# CurrentSensors.net
KiCad netlist of a schematic drawn in Altium Designer
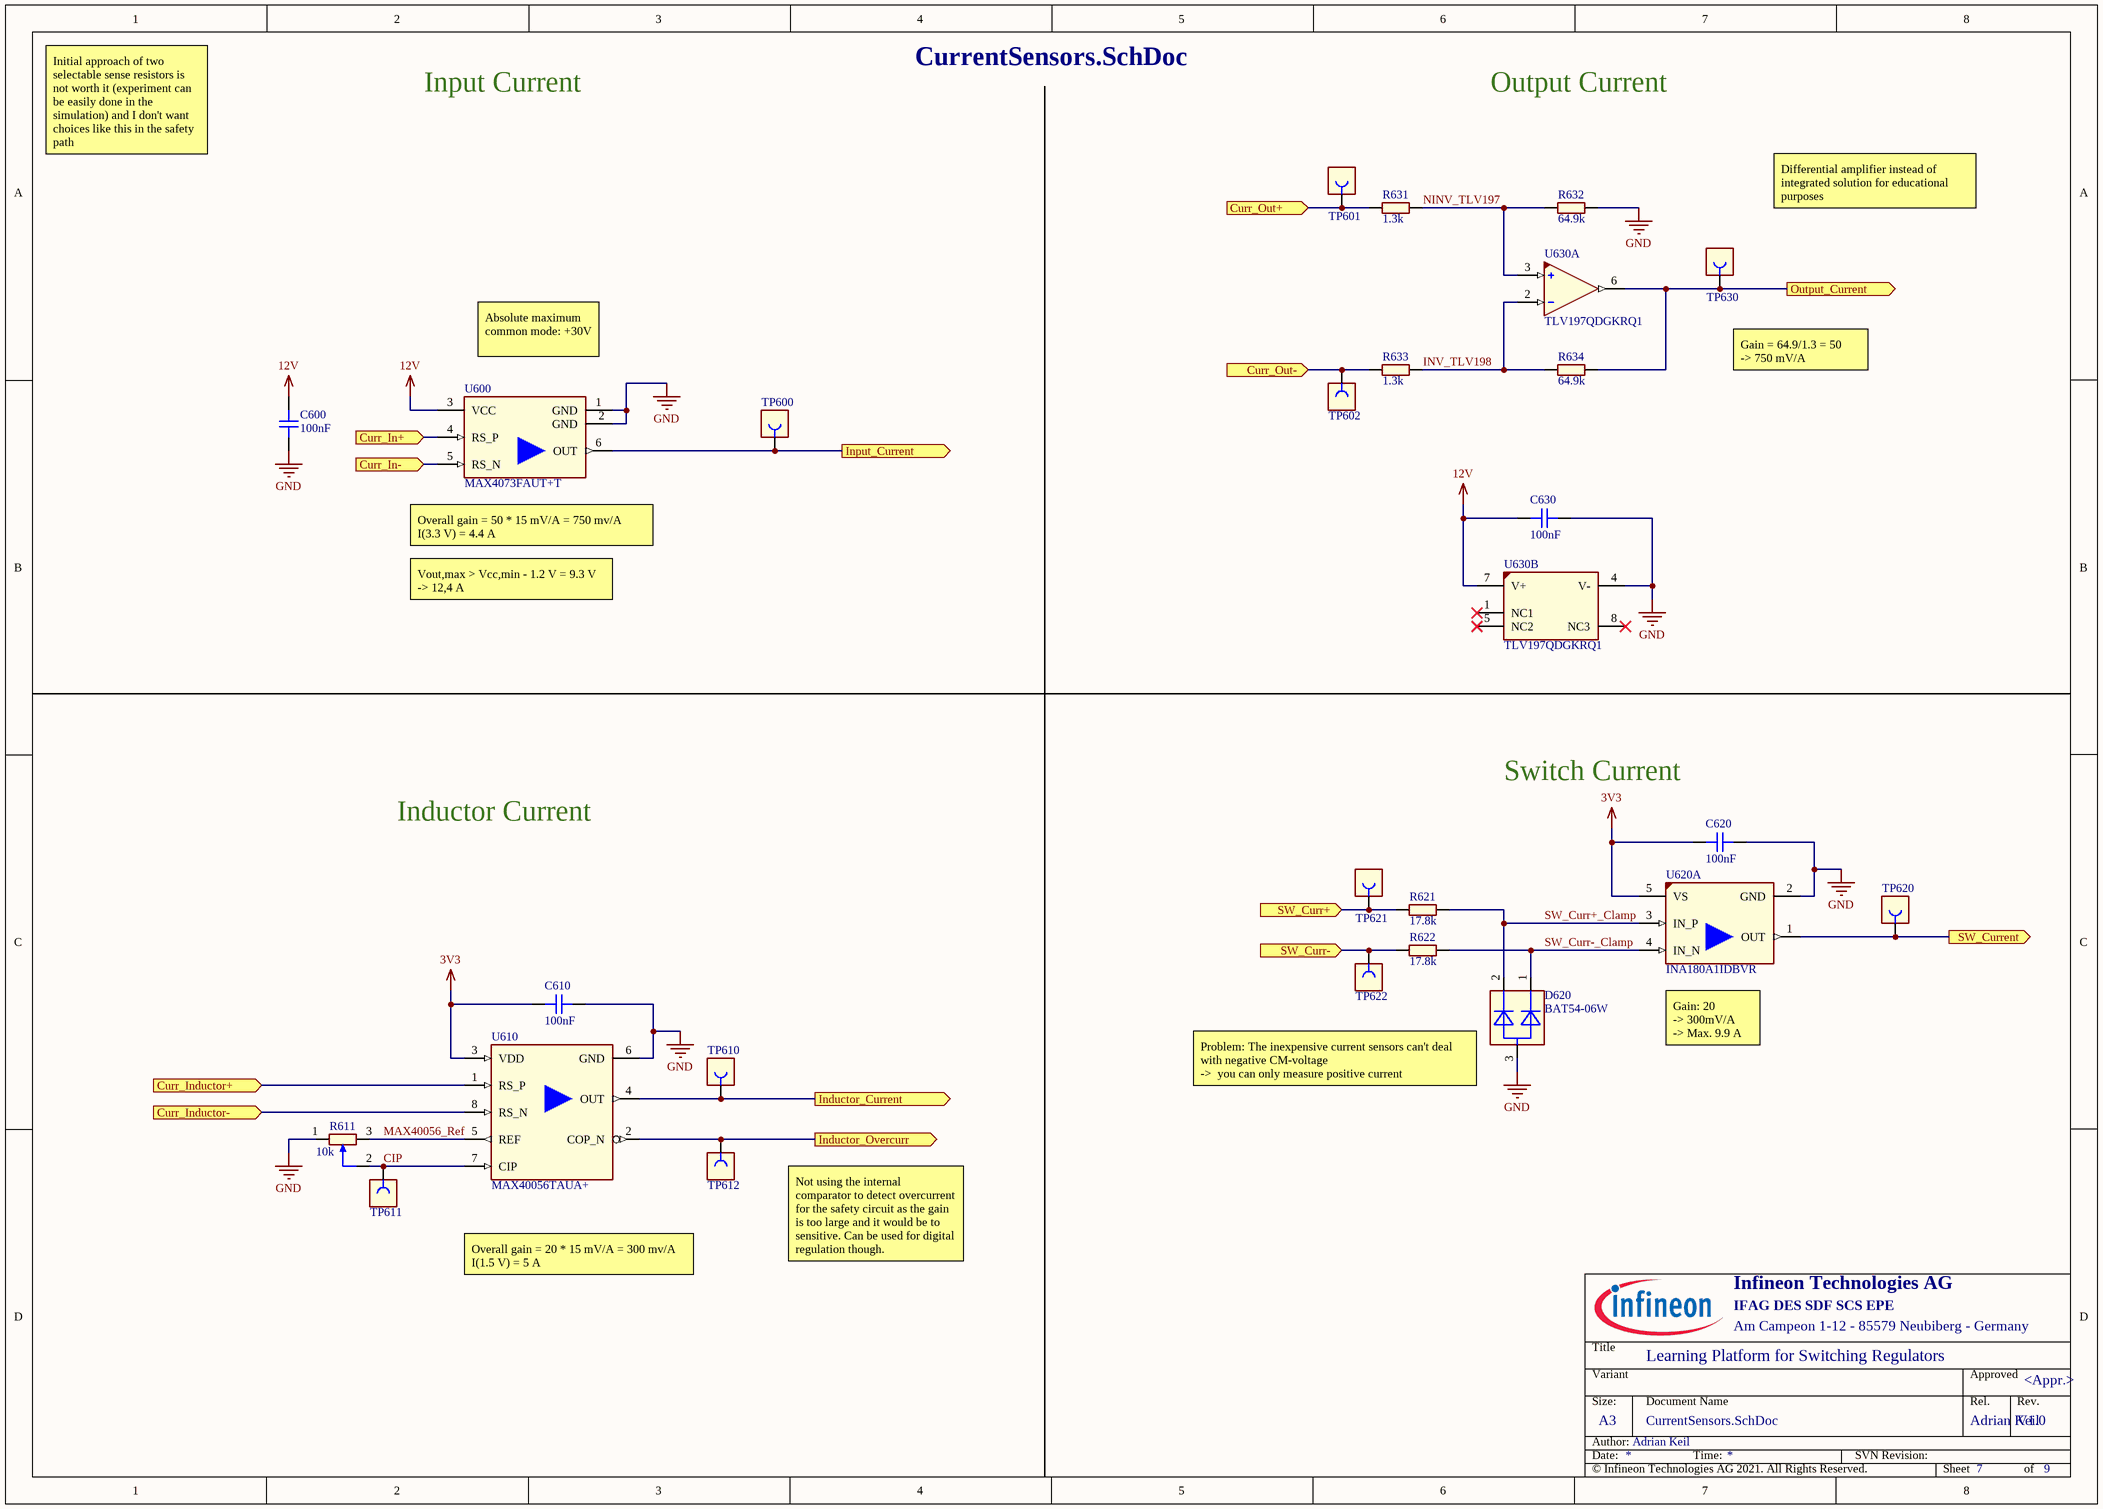
[diagram p0: CurrentSensors.SchDoc]

(export (version "E")
  (design (tool "Eeschema 10.0.6"))
  (components
    (comp (ref "C600")
      (value "100nF")
      (footprint "CAPC1608X90N-2")
      (description "CAP / CERA / 100nF / 50V / 10% / X7R (EIA) / -55°C to 125°C / 0603 / SMD / -")
      (fields (field (name "MANUFACTURER") "AVX"))
      (libsource (lib "PCBLibraryData") (part "CAP-SGL-STD-02P_00000001"))
    )
    (comp (ref "C610")
      (value "100nF")
      (footprint "CAPC1608X90N-2")
      (description "CAP / CERA / 100nF / 50V / 10% / X7R (EIA) / -55°C to 125°C / 0603 / SMD / -")
      (fields (field (name "MANUFACTURER") "AVX"))
      (libsource (lib "PCBLibraryData") (part "CAP-SGL-STD-02P_00000001"))
    )
    (comp (ref "C620")
      (value "100nF")
      (footprint "CAPC1608X90N-2")
      (description "CAP / CERA / 100nF / 50V / 10% / X7R (EIA) / -55°C to 125°C / 0603 / SMD / -")
      (fields (field (name "MANUFACTURER") "AVX"))
      (libsource (lib "PCBLibraryData") (part "CAP-SGL-STD-02P_00000001"))
    )
    (comp (ref "C630")
      (value "100nF")
      (footprint "CAPC1608X90N-2")
      (description "CAP / CERA / 100nF / 50V / 10% / X7R (EIA) / -55°C to 125°C / 0603 / SMD / -")
      (fields (field (name "MANUFACTURER") "AVX"))
      (libsource (lib "PCBLibraryData") (part "CAP-SGL-STD-02P_00000001"))
    )
    (comp (ref "D620")
      (value "BAT54-06W")
      (footprint "SOT65P210X100-3N-1-V")
      (description "Silicon Schottky Diodes")
      (fields (field (name "MANUFACTURER") "Infineon Technologies"))
      (libsource (lib "PCBLibraryData") (part "d_dual_c1c2a3_3p"))
    )
    (comp (ref "R611")
      (value "10k")
      (footprint "POT-SMD-3361P")
      (fields (field (name "MANUFACTURER") "Bourns"))
      (libsource (lib "PCBLibraryData") (part "RES-SGL-VAR-03P_00000026"))
    )
    (comp (ref "R621")
      (value "17.8k")
      (footprint "RESC1609X50N")
      (description "RES / STD / 17.8k / 100mW / 1% / 100ppm/K / -55°C to 155°C / 0603 / SMD / -")
      (fields (field (name "LEGACY PARTNUMBER") "RES01801283") (field (name "MANUFACTURER") "Vishay"))
      (libsource (lib "") (part "RES-SGL-STD-02P_00000006_1"))
    )
    (comp (ref "R622")
      (value "17.8k")
      (footprint "RESC1609X50N")
      (description "RES / STD / 17.8k / 100mW / 1% / 100ppm/K / -55°C to 155°C / 0603 / SMD / -")
      (fields (field (name "LEGACY PARTNUMBER") "RES01801283") (field (name "MANUFACTURER") "Vishay"))
      (libsource (lib "") (part "RES-SGL-STD-02P_00000006_1"))
    )
    (comp (ref "R631")
      (value "1.3k")
      (footprint "RESC1609X50N")
      (description "RES / STD / 1.3k / 100mW / 1% / 100ppm/K / -55°C to 155°C / 0603 / SMD / -")
      (fields (field (name "LEGACY PARTNUMBER") "RES01801155") (field (name "MANUFACTURER") "Vishay"))
      (libsource (lib "PCBLibraryData") (part "RES-SGL-STD-02P_00000006"))
    )
    (comp (ref "R632")
      (value "64.9k")
      (footprint "RESC1609X50N")
      (description "RES / STD / 64.9k / 100mW / 1% / 100ppm/K / -55°C to 155°C / 0603 / SMD / -")
      (fields (field (name "LEGACY PARTNUMBER") "RES01801350") (field (name "MANUFACTURER") "Vishay"))
      (libsource (lib "") (part "RES-SGL-STD-02P_00000006_1"))
    )
    (comp (ref "R633")
      (value "1.3k")
      (footprint "RESC1609X50N")
      (description "RES / STD / 1.3k / 100mW / 1% / 100ppm/K / -55°C to 155°C / 0603 / SMD / -")
      (fields (field (name "LEGACY PARTNUMBER") "RES01801155") (field (name "MANUFACTURER") "Vishay"))
      (libsource (lib "PCBLibraryData") (part "RES-SGL-STD-02P_00000006"))
    )
    (comp (ref "R634")
      (value "64.9k")
      (footprint "RESC1609X50N")
      (description "RES / STD / 64.9k / 100mW / 1% / 100ppm/K / -55°C to 155°C / 0603 / SMD / -")
      (fields (field (name "LEGACY PARTNUMBER") "RES01801350") (field (name "MANUFACTURER") "Vishay"))
      (libsource (lib "PCBLibraryData") (part "RES-SGL-STD-02P_00000006"))
    )
    (comp (ref "TP600")
      (value "S1751-46R")
      (footprint "CON-SMD-TT-S1751-46")
      (description "Test Terminal, Surface Mount (Tape and Reeled Components)")
      (fields (field (name "LEGACY PARTNUMBER") "CON01501015") (field (name "MANUFACTURER") "Harwin"))
      (libsource (lib "") (part "connector_1_f_1"))
    )
    (comp (ref "TP601")
      (value "S1751-46R")
      (footprint "CON-SMD-TT-S1751-46")
      (description "Test Terminal, Surface Mount (Tape and Reeled Components)")
      (fields (field (name "LEGACY PARTNUMBER") "CON01501015") (field (name "MANUFACTURER") "Harwin"))
      (libsource (lib "") (part "connector_1_f_1"))
    )
    (comp (ref "TP602")
      (value "S1751-46R")
      (footprint "CON-SMD-TT-S1751-46")
      (description "Test Terminal, Surface Mount (Tape and Reeled Components)")
      (fields (field (name "LEGACY PARTNUMBER") "CON01501015") (field (name "MANUFACTURER") "Harwin"))
      (libsource (lib "PCBLibraryData") (part "connector_1_f"))
    )
    (comp (ref "TP610")
      (value "S1751-46R")
      (footprint "CON-SMD-TT-S1751-46")
      (description "Test Terminal, Surface Mount (Tape and Reeled Components)")
      (fields (field (name "LEGACY PARTNUMBER") "CON01501015") (field (name "MANUFACTURER") "Harwin"))
      (libsource (lib "") (part "connector_1_f_1"))
    )
    (comp (ref "TP611")
      (value "S1751-46R")
      (footprint "CON-SMD-TT-S1751-46")
      (description "Test Terminal, Surface Mount (Tape and Reeled Components)")
      (fields (field (name "LEGACY PARTNUMBER") "CON01501015") (field (name "MANUFACTURER") "Harwin"))
      (libsource (lib "PCBLibraryData") (part "connector_1_f"))
    )
    (comp (ref "TP612")
      (value "S1751-46R")
      (footprint "CON-SMD-TT-S1751-46")
      (description "Test Terminal, Surface Mount (Tape and Reeled Components)")
      (fields (field (name "LEGACY PARTNUMBER") "CON01501015") (field (name "MANUFACTURER") "Harwin"))
      (libsource (lib "PCBLibraryData") (part "connector_1_f"))
    )
    (comp (ref "TP620")
      (value "S1751-46R")
      (footprint "CON-SMD-TT-S1751-46")
      (description "Test Terminal, Surface Mount (Tape and Reeled Components)")
      (fields (field (name "LEGACY PARTNUMBER") "CON01501015") (field (name "MANUFACTURER") "Harwin"))
      (libsource (lib "") (part "connector_1_f_1"))
    )
    (comp (ref "TP621")
      (value "S1751-46R")
      (footprint "CON-SMD-TT-S1751-46")
      (description "Test Terminal, Surface Mount (Tape and Reeled Components)")
      (fields (field (name "LEGACY PARTNUMBER") "CON01501015") (field (name "MANUFACTURER") "Harwin"))
      (libsource (lib "") (part "connector_1_f_1"))
    )
    (comp (ref "TP622")
      (value "S1751-46R")
      (footprint "CON-SMD-TT-S1751-46")
      (description "Test Terminal, Surface Mount (Tape and Reeled Components)")
      (fields (field (name "LEGACY PARTNUMBER") "CON01501015") (field (name "MANUFACTURER") "Harwin"))
      (libsource (lib "PCBLibraryData") (part "connector_1_f"))
    )
    (comp (ref "TP630")
      (value "S1751-46R")
      (footprint "CON-SMD-TT-S1751-46")
      (description "Test Terminal, Surface Mount (Tape and Reeled Components)")
      (fields (field (name "LEGACY PARTNUMBER") "CON01501015") (field (name "MANUFACTURER") "Harwin"))
      (libsource (lib "") (part "connector_1_f_1"))
    )
    (comp (ref "U600")
      (value "MAX4073FAUT+T")
      (footprint "SOT95P280X145-6N-2-V")
      (description "Low-Cost, Voltage-Output, High-Side Current-Sense Amplifier")
      (fields (field (name "MANUFACTURER") "Maxim Integrated Products"))
      (libsource (lib "PCBLibraryData") (part "MAX4073xAUT"))
    )
    (comp (ref "U610")
      (value "MAX40056TAUA+")
      (footprint "SOP65P490X110-8N-4")
      (description "Current Sense Amplifiers Current-Sense Amplifier W / PWM Rejection")
      (fields (field (name "MANUFACTURER") "Maxim Integrated Products"))
      (libsource (lib "PCBLibraryData") (part "MAX40056xAUA"))
    )
    (comp (ref "U620")
      (value "INA180A1IDBVR")
      (footprint "SOT95P280X145-5N-2")
      (description "Low- and High-Side Voltage Output, Current-Sense Amplifier")
      (fields (field (name "MANUFACTURER") "Texas Instruments"))
      (libsource (lib "PCBLibraryData") (part "INA293A"))
    )
    (comp (ref "U630")
      (value "TLV197QDGKRQ1")
      (footprint "SOP65P490X110-8N-V")
      (fields (field (name "MANUFACTURER") "Texas Instruments"))
      (libsource (lib "PCBLibraryData") (part "OPA140AID"))
    )
  )
  (nets
    (net (code "1") (name "/CIP") (class "Default")
      (node (ref "R611") (pin "2") (pinfunction "2_2") (pintype "passive"))
      (node (ref "TP611") (pin "1") (pinfunction "1_1") (pintype "passive"))
      (node (ref "U610") (pin "7") (pinfunction "CIP_7") (pintype "input"))
    )
    (net (code "2") (name "/Curr_In+") (class "Default")
      (node (ref "U600") (pin "4") (pinfunction "RS_P_4") (pintype "input"))
    )
    (net (code "3") (name "/Curr_In-") (class "Default")
      (node (ref "U600") (pin "5") (pinfunction "RS_N_5") (pintype "input"))
    )
    (net (code "4") (name "/Curr_Inductor+") (class "Default")
      (node (ref "U610") (pin "1") (pinfunction "RS_P_1") (pintype "input"))
    )
    (net (code "5") (name "/Curr_Inductor-") (class "Default")
      (node (ref "U610") (pin "8") (pinfunction "RS_N_8") (pintype "input"))
    )
    (net (code "6") (name "/Curr_Out+") (class "Default")
      (node (ref "R631") (pin "1") (pinfunction "1_1") (pintype "passive"))
      (node (ref "TP601") (pin "1") (pinfunction "1_1") (pintype "passive"))
    )
    (net (code "7") (name "/Curr_Out-") (class "Default")
      (node (ref "R633") (pin "1") (pinfunction "1_1") (pintype "passive"))
      (node (ref "TP602") (pin "1") (pinfunction "1_1") (pintype "passive"))
    )
    (net (code "8") (name "/INV_TLV198") (class "Default")
      (node (ref "R633") (pin "2") (pinfunction "2_2") (pintype "passive"))
      (node (ref "R634") (pin "1") (pinfunction "1_1") (pintype "passive"))
      (node (ref "U630") (pin "2") (pinfunction "IN_N_2") (pintype "input"))
    )
    (net (code "9") (name "/Inductor_Current") (class "Default")
      (node (ref "TP610") (pin "1") (pinfunction "1_1") (pintype "passive"))
      (node (ref "U610") (pin "4") (pinfunction "OUT_4") (pintype "output"))
    )
    (net (code "10") (name "/Inductor_Overcurr") (class "Default")
      (node (ref "TP612") (pin "1") (pinfunction "1_1") (pintype "passive"))
      (node (ref "U610") (pin "2") (pinfunction "COP_N_2") (pintype "output"))
    )
    (net (code "11") (name "/Input_Current") (class "Default")
      (node (ref "TP600") (pin "1") (pinfunction "1_1") (pintype "passive"))
      (node (ref "U600") (pin "6") (pinfunction "OUT_6") (pintype "output"))
    )
    (net (code "12") (name "/MAX40056_Ref") (class "Default")
      (node (ref "R611") (pin "3") (pinfunction "3_3") (pintype "passive"))
      (node (ref "U610") (pin "5") (pinfunction "REF_5") (pintype "output"))
    )
    (net (code "13") (name "/NINV_TLV197") (class "Default")
      (node (ref "R631") (pin "2") (pinfunction "2_2") (pintype "passive"))
      (node (ref "R632") (pin "2") (pinfunction "2_2") (pintype "passive"))
      (node (ref "U630") (pin "3") (pinfunction "IN_P_3") (pintype "input"))
    )
    (net (code "14") (name "/Output_Current") (class "Default")
      (node (ref "R634") (pin "2") (pinfunction "2_2") (pintype "passive"))
      (node (ref "TP630") (pin "1") (pinfunction "1_1") (pintype "passive"))
      (node (ref "U630") (pin "6") (pinfunction "OUT_6") (pintype "output"))
    )
    (net (code "15") (name "/SW_Curr+") (class "Default")
      (node (ref "R621") (pin "2") (pinfunction "2_2") (pintype "passive"))
      (node (ref "TP621") (pin "1") (pinfunction "1_1") (pintype "passive"))
    )
    (net (code "16") (name "/SW_Curr+_Clamp") (class "Default")
      (node (ref "D620") (pin "2") (pinfunction "CATHODE2_2") (pintype "passive"))
      (node (ref "R621") (pin "1") (pinfunction "1_1") (pintype "passive"))
      (node (ref "U620") (pin "3") (pinfunction "IN_P_3") (pintype "input"))
    )
    (net (code "17") (name "/SW_Curr-") (class "Default")
      (node (ref "R622") (pin "2") (pinfunction "2_2") (pintype "passive"))
      (node (ref "TP622") (pin "1") (pinfunction "1_1") (pintype "passive"))
    )
    (net (code "18") (name "/SW_Curr-_Clamp") (class "Default")
      (node (ref "D620") (pin "1") (pinfunction "CATHODE1_1") (pintype "passive"))
      (node (ref "R622") (pin "1") (pinfunction "1_1") (pintype "passive"))
      (node (ref "U620") (pin "4") (pinfunction "IN_N_4") (pintype "input"))
    )
    (net (code "19") (name "/SW_Current") (class "Default")
      (node (ref "TP620") (pin "1") (pinfunction "1_1") (pintype "passive"))
      (node (ref "U620") (pin "1") (pinfunction "OUT_1") (pintype "output"))
    )
    (net (code "20") (name "3V3") (class "Default")
      (node (ref "C610") (pin "2") (pinfunction "2_2") (pintype "passive"))
      (node (ref "C620") (pin "2") (pinfunction "2_2") (pintype "passive"))
      (node (ref "U610") (pin "3") (pinfunction "VDD_3") (pintype "input"))
      (node (ref "U620") (pin "5") (pinfunction "VS_5") (pintype "power_in"))
    )
    (net (code "21") (name "12V") (class "Default")
      (node (ref "C600") (pin "2") (pinfunction "2_2") (pintype "passive"))
      (node (ref "C630") (pin "2") (pinfunction "2_2") (pintype "passive"))
      (node (ref "U600") (pin "3") (pinfunction "VCC_3") (pintype "power_in"))
      (node (ref "U630") (pin "7") (pinfunction "V+_7") (pintype "power_in"))
    )
    (net (code "22") (name "GND") (class "Default")
      (node (ref "C600") (pin "1") (pinfunction "1_1") (pintype "passive"))
      (node (ref "C610") (pin "1") (pinfunction "1_1") (pintype "passive"))
      (node (ref "C620") (pin "1") (pinfunction "1_1") (pintype "passive"))
      (node (ref "C630") (pin "1") (pinfunction "1_1") (pintype "passive"))
      (node (ref "D620") (pin "3") (pinfunction "ANODE_3") (pintype "passive"))
      (node (ref "R611") (pin "1") (pinfunction "1_1") (pintype "passive"))
      (node (ref "R632") (pin "1") (pinfunction "1_1") (pintype "passive"))
      (node (ref "U600") (pin "1") (pinfunction "GND_1") (pintype "power_in"))
      (node (ref "U600") (pin "2") (pinfunction "GND_2") (pintype "power_in"))
      (node (ref "U610") (pin "6") (pinfunction "GND_6") (pintype "power_in"))
      (node (ref "U620") (pin "2") (pinfunction "GND_2") (pintype "power_in"))
      (node (ref "U630") (pin "4") (pinfunction "V-_4") (pintype "power_in"))
    )
    (net (code "23") (name "unconnected-(U630B-NC1-Pad1)") (class "Default")
      (node (ref "U630") (pin "1") (pinfunction "NC1_1") (pintype "passive+no_connect"))
    )
    (net (code "24") (name "unconnected-(U630B-NC2-Pad5)") (class "Default")
      (node (ref "U630") (pin "5") (pinfunction "NC2_5") (pintype "passive+no_connect"))
    )
    (net (code "25") (name "unconnected-(U630B-NC3-Pad8)") (class "Default")
      (node (ref "U630") (pin "8") (pinfunction "NC3_8") (pintype "passive+no_connect"))
    )
  )
)
